# Group_02.net
KiCad netlist of a schematic drawn in EAGLE
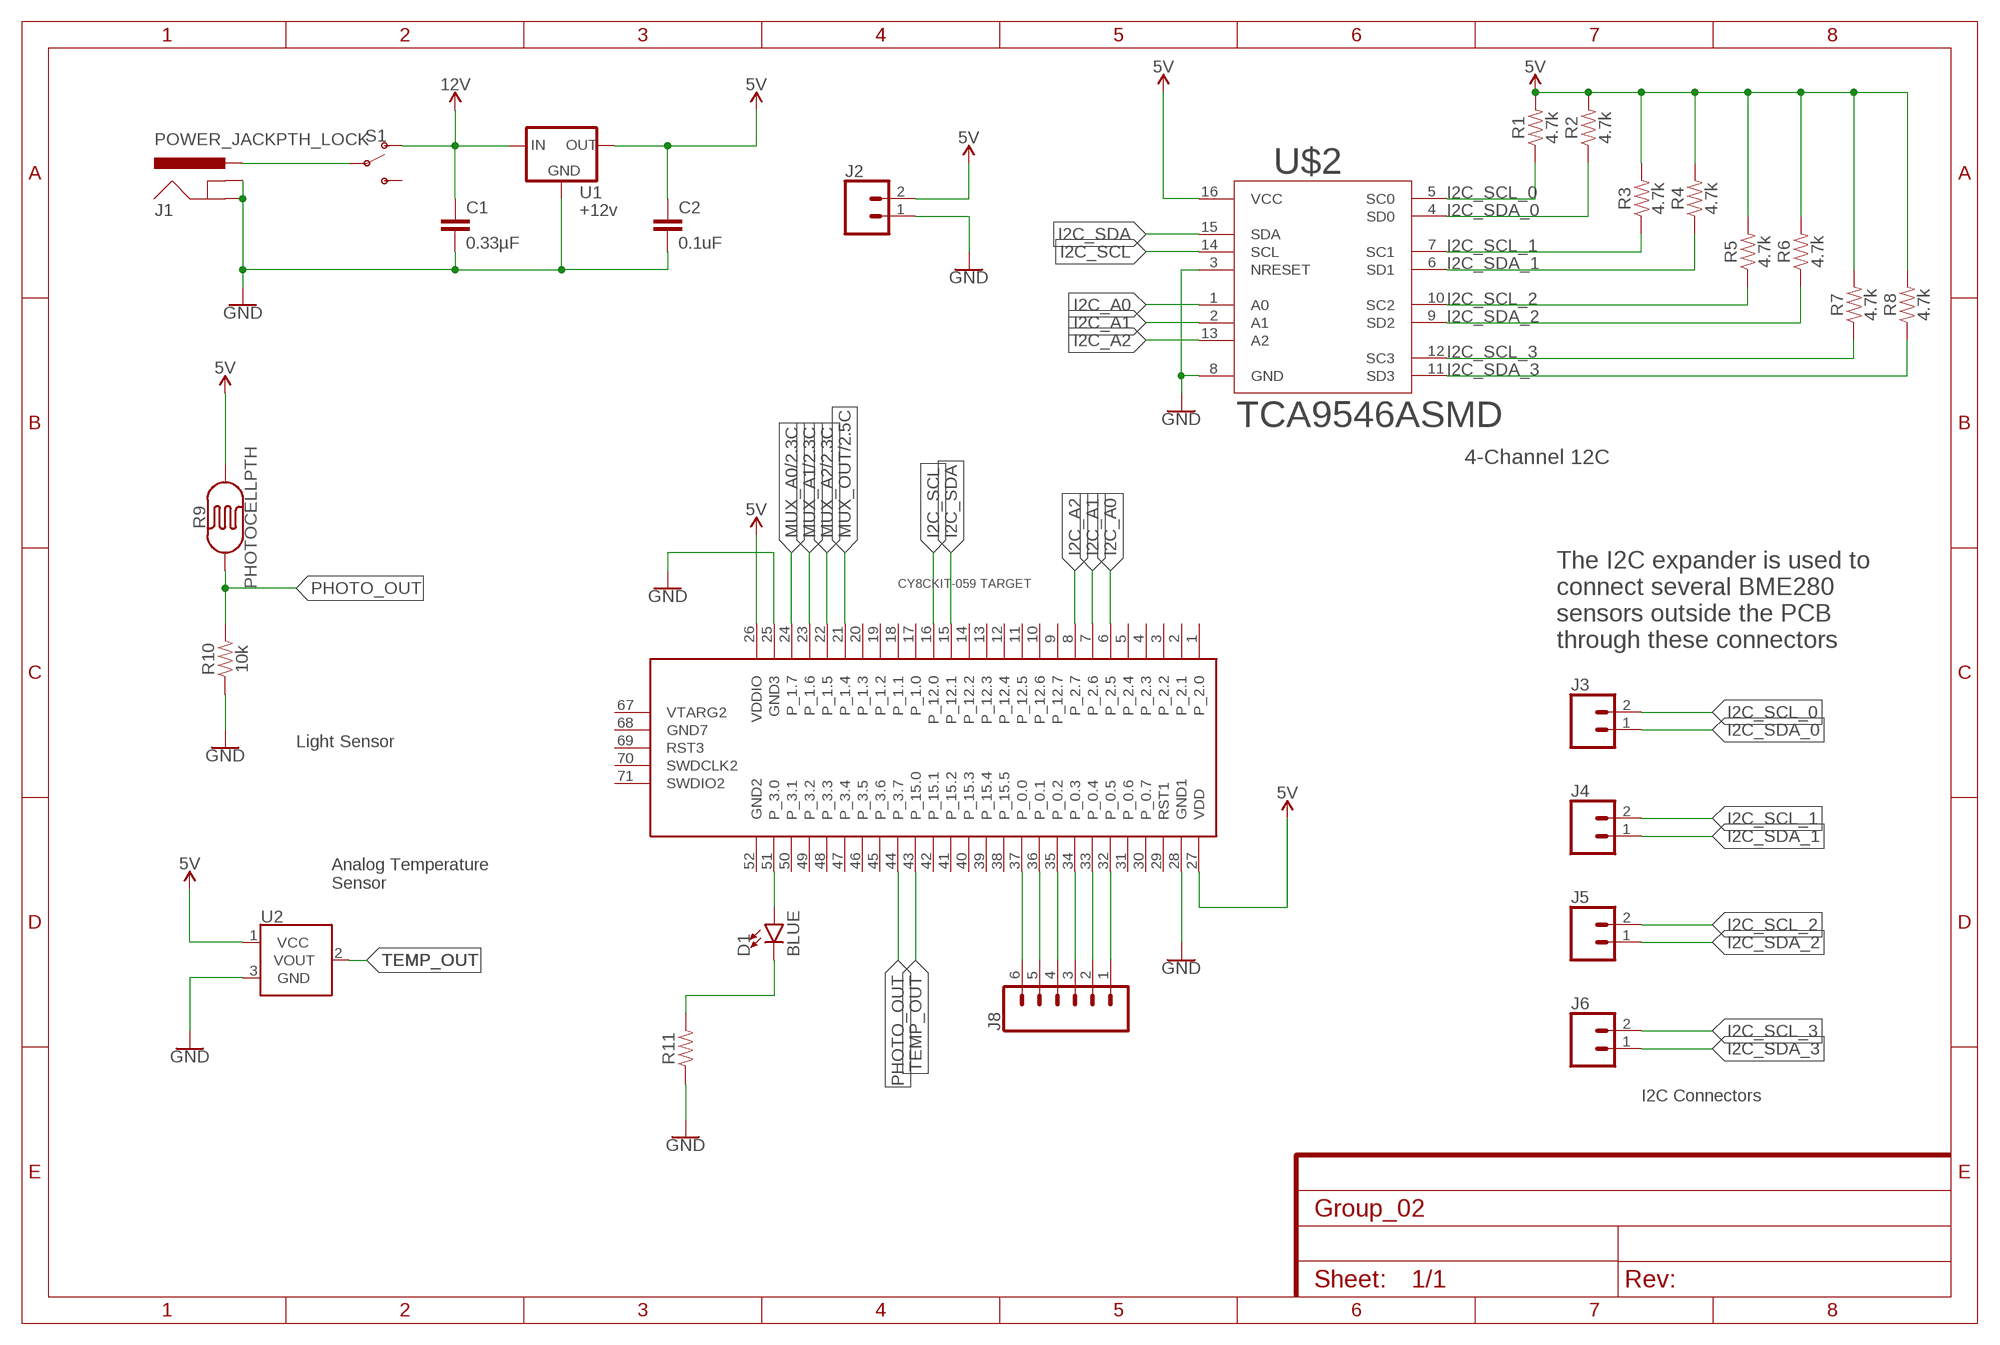
[diagram p0: schematic, sheet 1, part 1 of 2]
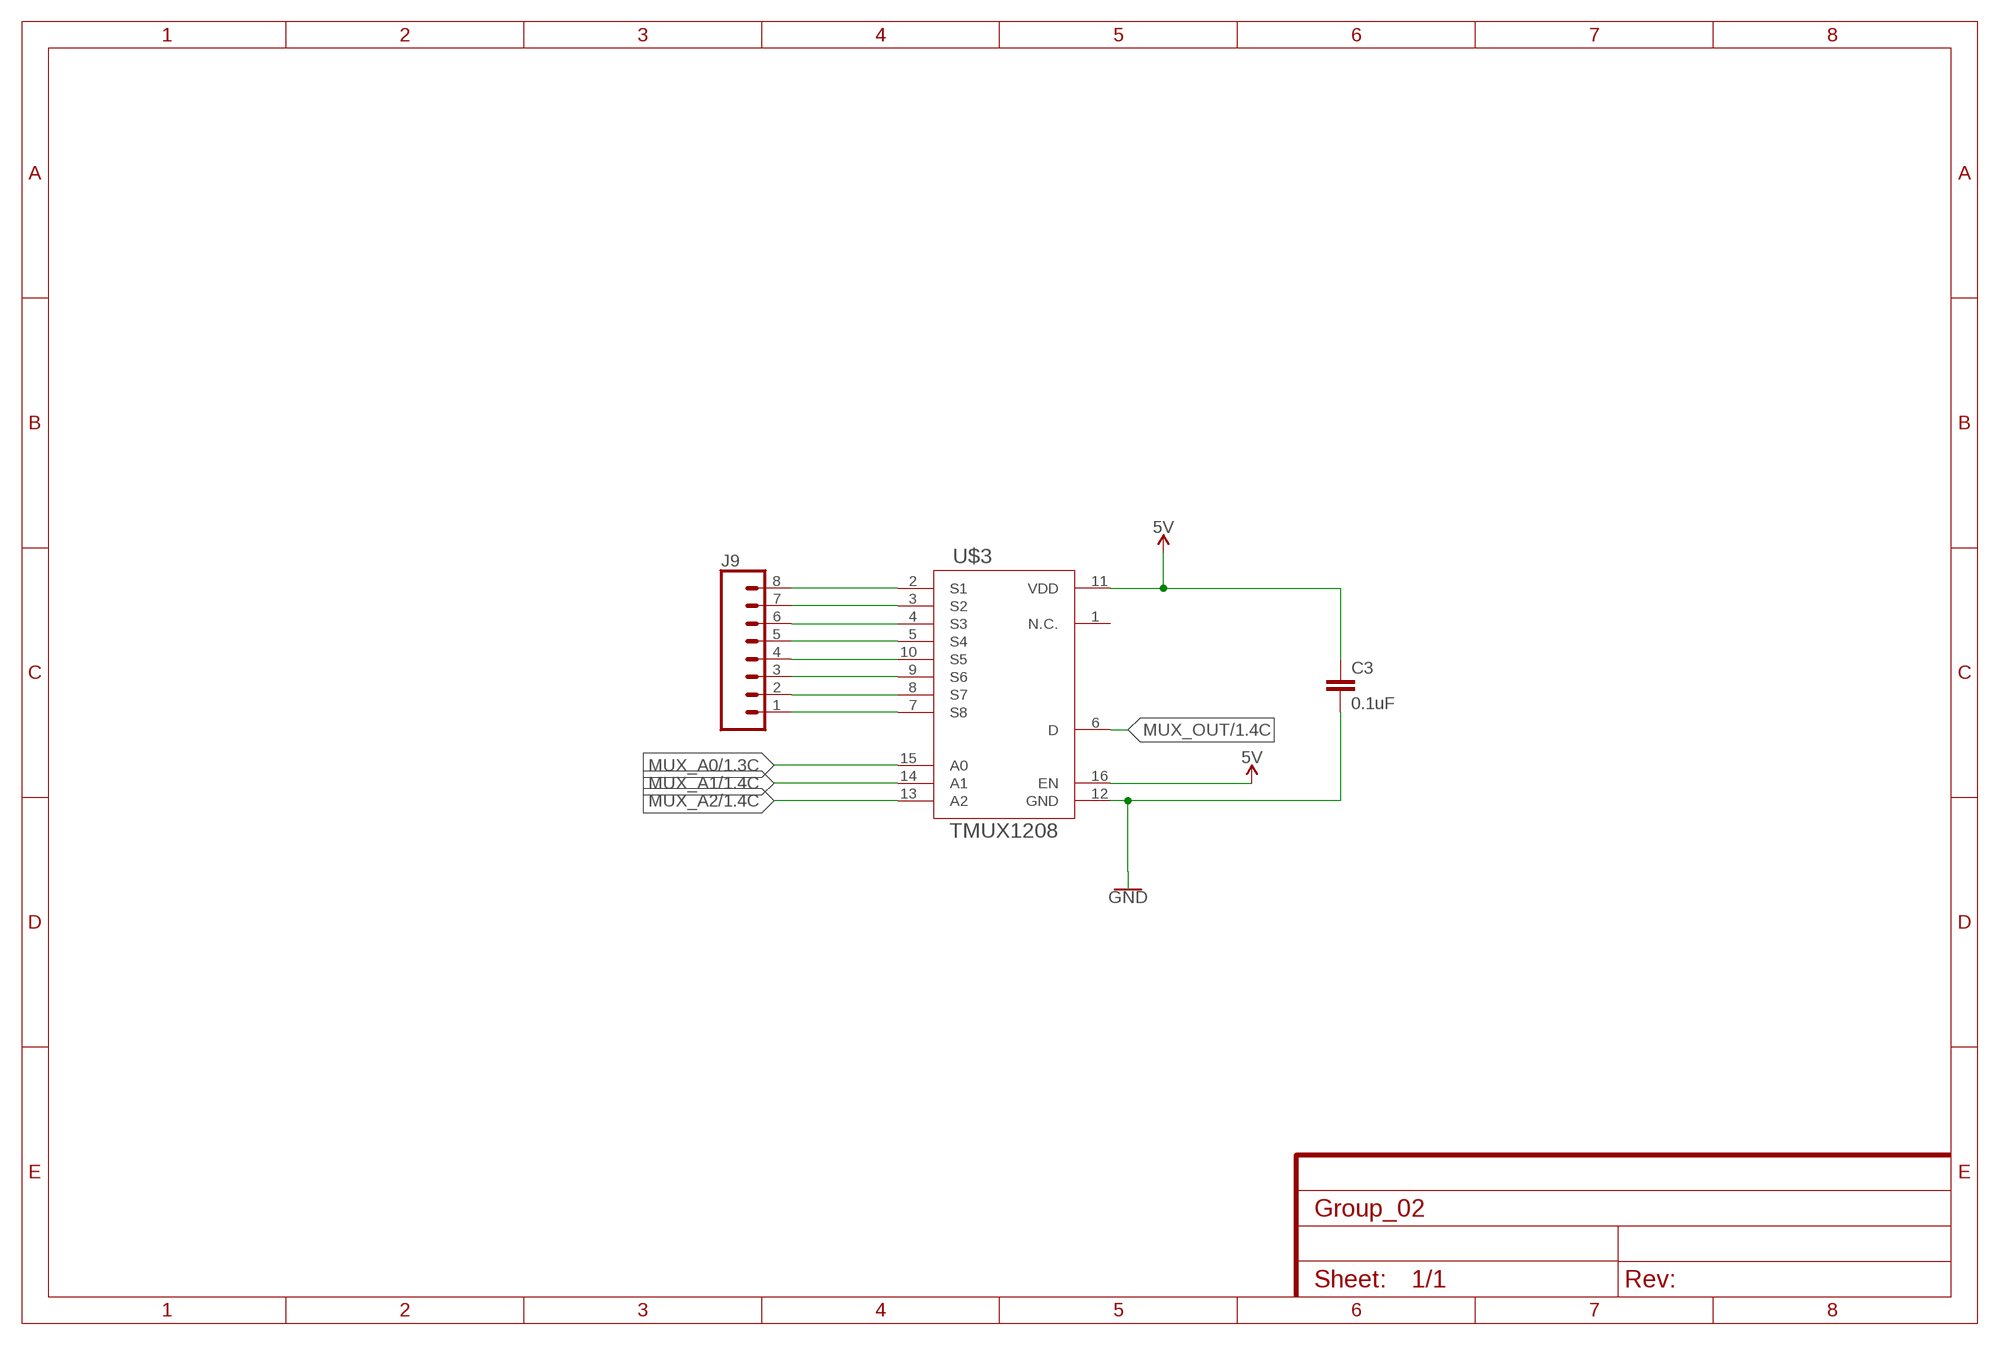
[diagram p1: schematic, sheet 1, part 2 of 2]

(export (version "E")
  (design (tool "Eeschema 10.0.6"))
  (components
    (comp (ref "C1")
      (value "0.33µF")
      (footprint "eagle-import:0805")
      (libsource (lib "eagle-import") (part "0.33UF/330NF-0805-50V-10%"))
    )
    (comp (ref "C2")
      (value "0.1uF")
      (footprint "eagle-import:CAP-PTH-SMALL-KIT")
      (libsource (lib "eagle-import") (part "0.1UF-KIT-EZ-50V-20%"))
    )
    (comp (ref "C3")
      (value "0.1uF")
      (footprint "eagle-import:CAP-PTH-SMALL-KIT")
      (libsource (lib "eagle-import") (part "0.1UF-KIT-EZ-50V-20%"))
    )
    (comp (ref "D1")
      (value "BLUE")
      (footprint "eagle-import:LED-1206")
      (libsource (lib "eagle-import") (part "LED-BLUE1206"))
    )
    (comp (ref "J1")
      (value "POWER_JACKPTH_LOCK")
      (footprint "eagle-import:POWER_JACK_PTH_LOCK")
      (libsource (lib "eagle-import") (part "POWER_JACKPTH_LOCK"))
    )
    (comp (ref "J2")
      (value "CONN_02")
      (footprint "eagle-import:1X02")
      (libsource (lib "eagle-import") (part "CONN_02"))
    )
    (comp (ref "J3")
      (value "CONN_02")
      (footprint "eagle-import:1X02")
      (libsource (lib "eagle-import") (part "CONN_02"))
    )
    (comp (ref "J4")
      (value "CONN_02")
      (footprint "eagle-import:1X02")
      (libsource (lib "eagle-import") (part "CONN_02"))
    )
    (comp (ref "J5")
      (value "CONN_02")
      (footprint "eagle-import:1X02")
      (libsource (lib "eagle-import") (part "CONN_02"))
    )
    (comp (ref "J6")
      (value "CONN_02")
      (footprint "eagle-import:1X02")
      (libsource (lib "eagle-import") (part "CONN_02"))
    )
    (comp (ref "J8")
      (value "CONN_06LOCK")
      (footprint "eagle-import:1X06_LOCK")
      (libsource (lib "eagle-import") (part "CONN_06LOCK"))
    )
    (comp (ref "J9")
      (value "CONN_08LOCK")
      (footprint "eagle-import:1X08_LOCK")
      (libsource (lib "eagle-import") (part "CONN_08LOCK"))
    )
    (comp (ref "R1")
      (value "4.7k")
      (footprint "eagle-import:0603")
      (libsource (lib "eagle-import") (part "4.7KOHM-0603-1/10W-1%"))
    )
    (comp (ref "R2")
      (value "4.7k")
      (footprint "eagle-import:0603")
      (libsource (lib "eagle-import") (part "4.7KOHM-0603-1/10W-1%"))
    )
    (comp (ref "R3")
      (value "4.7k")
      (footprint "eagle-import:0603")
      (libsource (lib "eagle-import") (part "4.7KOHM-0603-1/10W-1%"))
    )
    (comp (ref "R4")
      (value "4.7k")
      (footprint "eagle-import:0603")
      (libsource (lib "eagle-import") (part "4.7KOHM-0603-1/10W-1%"))
    )
    (comp (ref "R5")
      (value "4.7k")
      (footprint "eagle-import:0603")
      (libsource (lib "eagle-import") (part "4.7KOHM-0603-1/10W-1%"))
    )
    (comp (ref "R6")
      (value "4.7k")
      (footprint "eagle-import:0603")
      (libsource (lib "eagle-import") (part "4.7KOHM-0603-1/10W-1%"))
    )
    (comp (ref "R7")
      (value "4.7k")
      (footprint "eagle-import:0603")
      (libsource (lib "eagle-import") (part "4.7KOHM-0603-1/10W-1%"))
    )
    (comp (ref "R8")
      (value "4.7k")
      (footprint "eagle-import:0603")
      (libsource (lib "eagle-import") (part "4.7KOHM-0603-1/10W-1%"))
    )
    (comp (ref "R9")
      (value "PHOTOCELLPTH")
      (footprint "eagle-import:PHOTOCELL")
      (libsource (lib "eagle-import") (part "PHOTOCELLPTH"))
    )
    (comp (ref "R10")
      (value "10k")
      (footprint "eagle-import:0603")
      (libsource (lib "eagle-import") (part "10KOHM-0603-1/10W-1%"))
    )
    (comp (ref "R11")
      (value "RESISTORAXIAL-0.3")
      (footprint "eagle-import:AXIAL-0.3")
      (libsource (lib "eagle-import") (part "RESISTORAXIAL-0.3"))
    )
    (comp (ref "S1")
      (value "SWITCH-SPDT-PTH-11.6X4.0MM")
      (footprint "eagle-import:SWITCH_SPDT_PTH_11.6X4.0MM")
      (libsource (lib "eagle-import") (part "SWITCH-SPDT-PTH-11.6X4.0MM"))
    )
    (comp (ref "U$1")
      (value "CY8CKIT-059_TARGET")
      (footprint "eagle-import:CY8CKIT-059_TARGET")
      (libsource (lib "eagle-import") (part "CY8CKIT-059_TARGET"))
    )
    (comp (ref "U$2")
      (value "TCA9546ASMD")
      (footprint "eagle-import:TSSOP-16")
      (libsource (lib "eagle-import") (part "TCA9546ASMD"))
    )
    (comp (ref "U$3")
      (value "TMUX1208")
      (footprint "eagle-import:QFN-16")
      (libsource (lib "eagle-import") (part "TMUX1208"))
    )
    (comp (ref "U1")
      (value "+12v")
      (footprint "eagle-import:TO-252")
      (libsource (lib "eagle-import") (part "V_REG_78XX7812"))
    )
    (comp (ref "U2")
      (value "TMP36GT9")
      (footprint "eagle-import:TO-92")
      (libsource (lib "eagle-import") (part "TMP36GT9"))
    )
  )
  (nets
    (net (code "1") (name "5V") (class "Default")
      (node (ref "C2") (pin "1") (pinfunction "1_1") (pintype "passive"))
      (node (ref "C3") (pin "1") (pinfunction "1_1") (pintype "passive"))
      (node (ref "J2") (pin "2") (pinfunction "2_2") (pintype "passive"))
      (node (ref "R1") (pin "2") (pinfunction "2_2") (pintype "passive"))
      (node (ref "R2") (pin "2") (pinfunction "2_2") (pintype "passive"))
      (node (ref "R3") (pin "2") (pinfunction "2_2") (pintype "passive"))
      (node (ref "R4") (pin "2") (pinfunction "2_2") (pintype "passive"))
      (node (ref "R5") (pin "2") (pinfunction "2_2") (pintype "passive"))
      (node (ref "R6") (pin "2") (pinfunction "2_2") (pintype "passive"))
      (node (ref "R7") (pin "2") (pinfunction "2_2") (pintype "passive"))
      (node (ref "R8") (pin "2") (pinfunction "2_2") (pintype "passive"))
      (node (ref "R9") (pin "2") (pinfunction "P$2_2") (pintype "bidirectional"))
      (node (ref "U$1") (pin "26") (pinfunction "VDDIO_26") (pintype "bidirectional"))
      (node (ref "U$1") (pin "27") (pinfunction "VDD_27") (pintype "bidirectional"))
      (node (ref "U$2") (pin "16") (pinfunction "VCC_16") (pintype "bidirectional"))
      (node (ref "U$3") (pin "11") (pinfunction "VDD_11") (pintype "bidirectional"))
      (node (ref "U$3") (pin "16") (pinfunction "EN_16") (pintype "bidirectional"))
      (node (ref "U1") (pin "2") (pinfunction "OUT_2") (pintype "passive"))
      (node (ref "U2") (pin "1") (pinfunction "VCC_1") (pintype "bidirectional"))
    )
    (net (code "2") (name "12V") (class "Default")
      (node (ref "C1") (pin "1") (pinfunction "1_1") (pintype "passive"))
      (node (ref "S1") (pin "1") (pinfunction "O_1") (pintype "passive"))
      (node (ref "U1") (pin "1") (pinfunction "IN_1") (pintype "input"))
    )
    (net (code "3") (name "GND") (class "Default")
      (node (ref "C1") (pin "2") (pinfunction "2_2") (pintype "passive"))
      (node (ref "C2") (pin "2") (pinfunction "2_2") (pintype "passive"))
      (node (ref "C3") (pin "2") (pinfunction "2_2") (pintype "passive"))
      (node (ref "J1") (pin "GND") (pinfunction "GND_GND") (pintype "bidirectional"))
      (node (ref "J1") (pin "GNDBREAK") (pinfunction "GNDBREAK_GNDBREAK") (pintype "bidirectional"))
      (node (ref "J2") (pin "1") (pinfunction "1_1") (pintype "passive"))
      (node (ref "R10") (pin "1") (pinfunction "1_1") (pintype "passive"))
      (node (ref "R11") (pin "P$1") (pinfunction "1_P$1") (pintype "passive"))
      (node (ref "U$1") (pin "25") (pinfunction "GND3_25") (pintype "bidirectional"))
      (node (ref "U$1") (pin "28") (pinfunction "GND1_28") (pintype "bidirectional"))
      (node (ref "U$2") (pin "3") (pinfunction "NRESET_3") (pintype "bidirectional"))
      (node (ref "U$2") (pin "8") (pinfunction "GND_8") (pintype "bidirectional"))
      (node (ref "U$3") (pin "12") (pinfunction "GND_12") (pintype "bidirectional"))
      (node (ref "U1") (pin "3") (pinfunction "GND_3") (pintype "input"))
      (node (ref "U2") (pin "3") (pinfunction "GND_3") (pintype "bidirectional"))
    )
    (net (code "4") (name "I2C_A0") (class "Default")
      (node (ref "U$1") (pin "6") (pinfunction "P_2.5_6") (pintype "bidirectional"))
      (node (ref "U$2") (pin "1") (pinfunction "A0_1") (pintype "bidirectional"))
    )
    (net (code "5") (name "I2C_A1") (class "Default")
      (node (ref "U$1") (pin "7") (pinfunction "P_2.6_7") (pintype "bidirectional"))
      (node (ref "U$2") (pin "2") (pinfunction "A1_2") (pintype "bidirectional"))
    )
    (net (code "6") (name "I2C_A2") (class "Default")
      (node (ref "U$1") (pin "8") (pinfunction "P_2.7_8") (pintype "bidirectional"))
      (node (ref "U$2") (pin "13") (pinfunction "A2_13") (pintype "bidirectional"))
    )
    (net (code "7") (name "I2C_SCL") (class "Default")
      (node (ref "U$1") (pin "16") (pinfunction "P_12.0_16") (pintype "bidirectional"))
      (node (ref "U$2") (pin "14") (pinfunction "SCL_14") (pintype "bidirectional"))
    )
    (net (code "8") (name "I2C_SCL_0") (class "Default")
      (node (ref "J3") (pin "2") (pinfunction "2_2") (pintype "passive"))
      (node (ref "R1") (pin "1") (pinfunction "1_1") (pintype "passive"))
      (node (ref "U$2") (pin "5") (pinfunction "SC0_5") (pintype "bidirectional"))
    )
    (net (code "9") (name "I2C_SCL_1") (class "Default")
      (node (ref "J4") (pin "2") (pinfunction "2_2") (pintype "passive"))
      (node (ref "R3") (pin "1") (pinfunction "1_1") (pintype "passive"))
      (node (ref "U$2") (pin "7") (pinfunction "SC1_7") (pintype "bidirectional"))
    )
    (net (code "10") (name "I2C_SCL_2") (class "Default")
      (node (ref "J5") (pin "2") (pinfunction "2_2") (pintype "passive"))
      (node (ref "R5") (pin "1") (pinfunction "1_1") (pintype "passive"))
      (node (ref "U$2") (pin "10") (pinfunction "SC2_10") (pintype "bidirectional"))
    )
    (net (code "11") (name "I2C_SCL_3") (class "Default")
      (node (ref "J6") (pin "2") (pinfunction "2_2") (pintype "passive"))
      (node (ref "R7") (pin "1") (pinfunction "1_1") (pintype "passive"))
      (node (ref "U$2") (pin "12") (pinfunction "SC3_12") (pintype "bidirectional"))
    )
    (net (code "12") (name "I2C_SDA") (class "Default")
      (node (ref "U$1") (pin "15") (pinfunction "P_12.1_15") (pintype "bidirectional"))
      (node (ref "U$2") (pin "15") (pinfunction "SDA_15") (pintype "bidirectional"))
    )
    (net (code "13") (name "I2C_SDA_0") (class "Default")
      (node (ref "J3") (pin "1") (pinfunction "1_1") (pintype "passive"))
      (node (ref "R2") (pin "1") (pinfunction "1_1") (pintype "passive"))
      (node (ref "U$2") (pin "4") (pinfunction "SD0_4") (pintype "bidirectional"))
    )
    (net (code "14") (name "I2C_SDA_1") (class "Default")
      (node (ref "J4") (pin "1") (pinfunction "1_1") (pintype "passive"))
      (node (ref "R4") (pin "1") (pinfunction "1_1") (pintype "passive"))
      (node (ref "U$2") (pin "6") (pinfunction "SD1_6") (pintype "bidirectional"))
    )
    (net (code "15") (name "I2C_SDA_2") (class "Default")
      (node (ref "J5") (pin "1") (pinfunction "1_1") (pintype "passive"))
      (node (ref "R6") (pin "1") (pinfunction "1_1") (pintype "passive"))
      (node (ref "U$2") (pin "9") (pinfunction "SD2_9") (pintype "bidirectional"))
    )
    (net (code "16") (name "I2C_SDA_3") (class "Default")
      (node (ref "J6") (pin "1") (pinfunction "1_1") (pintype "passive"))
      (node (ref "R8") (pin "1") (pinfunction "1_1") (pintype "passive"))
      (node (ref "U$2") (pin "11") (pinfunction "SD3_11") (pintype "bidirectional"))
    )
    (net (code "17") (name "MUX_A0{slash}1.3C") (class "Default")
      (node (ref "U$3") (pin "15") (pinfunction "A0_15") (pintype "bidirectional"))
    )
    (net (code "18") (name "MUX_A0{slash}2.3C") (class "Default")
      (node (ref "U$1") (pin "24") (pinfunction "P_1.7_24") (pintype "bidirectional"))
    )
    (net (code "19") (name "MUX_A1{slash}1.4C") (class "Default")
      (node (ref "U$3") (pin "14") (pinfunction "A1_14") (pintype "bidirectional"))
    )
    (net (code "20") (name "MUX_A1{slash}2.3C") (class "Default")
      (node (ref "U$1") (pin "23") (pinfunction "P_1.6_23") (pintype "bidirectional"))
    )
    (net (code "21") (name "MUX_A2{slash}1.4C") (class "Default")
      (node (ref "U$3") (pin "13") (pinfunction "A2_13") (pintype "bidirectional"))
    )
    (net (code "22") (name "MUX_A2{slash}2.3C") (class "Default")
      (node (ref "U$1") (pin "22") (pinfunction "P_1.5_22") (pintype "bidirectional"))
    )
    (net (code "23") (name "MUX_OUT{slash}1.4C") (class "Default")
      (node (ref "U$3") (pin "6") (pinfunction "D_6") (pintype "bidirectional"))
    )
    (net (code "24") (name "MUX_OUT{slash}2.5C") (class "Default")
      (node (ref "U$1") (pin "21") (pinfunction "P_1.4_21") (pintype "bidirectional"))
    )
    (net (code "25") (name "Net-(R11-2)") (class "Default")
      (node (ref "D1") (pin "C") (pinfunction "C_C") (pintype "passive"))
      (node (ref "R11") (pin "P$2") (pinfunction "2_P$2") (pintype "passive"))
    )
    (net (code "26") (name "Net-(S1-P)") (class "Default")
      (node (ref "J1") (pin "PWR") (pinfunction "PWR_PWR") (pintype "bidirectional"))
      (node (ref "S1") (pin "2") (pinfunction "P_2") (pintype "passive"))
    )
    (net (code "27") (name "Net-(U$1-P_0.0)") (class "Default")
      (node (ref "J8") (pin "6") (pinfunction "6_6") (pintype "passive"))
      (node (ref "U$1") (pin "37") (pinfunction "P_0.0_37") (pintype "bidirectional"))
    )
    (net (code "28") (name "Net-(U$1-P_0.1)") (class "Default")
      (node (ref "J8") (pin "5") (pinfunction "5_5") (pintype "passive"))
      (node (ref "U$1") (pin "36") (pinfunction "P_0.1_36") (pintype "bidirectional"))
    )
    (net (code "29") (name "Net-(U$1-P_0.2)") (class "Default")
      (node (ref "J8") (pin "4") (pinfunction "4_4") (pintype "passive"))
      (node (ref "U$1") (pin "35") (pinfunction "P_0.2_35") (pintype "bidirectional"))
    )
    (net (code "30") (name "Net-(U$1-P_0.3)") (class "Default")
      (node (ref "J8") (pin "3") (pinfunction "3_3") (pintype "passive"))
      (node (ref "U$1") (pin "34") (pinfunction "P_0.3_34") (pintype "bidirectional"))
    )
    (net (code "31") (name "Net-(U$1-P_0.4)") (class "Default")
      (node (ref "J8") (pin "2") (pinfunction "2_2") (pintype "passive"))
      (node (ref "U$1") (pin "33") (pinfunction "P_0.4_33") (pintype "bidirectional"))
    )
    (net (code "32") (name "Net-(U$1-P_0.5)") (class "Default")
      (node (ref "J8") (pin "1") (pinfunction "1_1") (pintype "passive"))
      (node (ref "U$1") (pin "32") (pinfunction "P_0.5_32") (pintype "bidirectional"))
    )
    (net (code "33") (name "Net-(U$1-P_3.0)") (class "Default")
      (node (ref "D1") (pin "A") (pinfunction "A_A") (pintype "passive"))
      (node (ref "U$1") (pin "51") (pinfunction "P_3.0_51") (pintype "bidirectional"))
    )
    (net (code "34") (name "Net-(U$3-S1)") (class "Default")
      (node (ref "J9") (pin "8") (pinfunction "8_8") (pintype "passive"))
      (node (ref "U$3") (pin "2") (pinfunction "S1_2") (pintype "bidirectional"))
    )
    (net (code "35") (name "Net-(U$3-S2)") (class "Default")
      (node (ref "J9") (pin "7") (pinfunction "7_7") (pintype "passive"))
      (node (ref "U$3") (pin "3") (pinfunction "S2_3") (pintype "bidirectional"))
    )
    (net (code "36") (name "Net-(U$3-S3)") (class "Default")
      (node (ref "J9") (pin "6") (pinfunction "6_6") (pintype "passive"))
      (node (ref "U$3") (pin "4") (pinfunction "S3_4") (pintype "bidirectional"))
    )
    (net (code "37") (name "Net-(U$3-S4)") (class "Default")
      (node (ref "J9") (pin "5") (pinfunction "5_5") (pintype "passive"))
      (node (ref "U$3") (pin "5") (pinfunction "S4_5") (pintype "bidirectional"))
    )
    (net (code "38") (name "Net-(U$3-S5)") (class "Default")
      (node (ref "J9") (pin "4") (pinfunction "4_4") (pintype "passive"))
      (node (ref "U$3") (pin "10") (pinfunction "S5_10") (pintype "bidirectional"))
    )
    (net (code "39") (name "Net-(U$3-S6)") (class "Default")
      (node (ref "J9") (pin "3") (pinfunction "3_3") (pintype "passive"))
      (node (ref "U$3") (pin "9") (pinfunction "S6_9") (pintype "bidirectional"))
    )
    (net (code "40") (name "Net-(U$3-S7)") (class "Default")
      (node (ref "J9") (pin "2") (pinfunction "2_2") (pintype "passive"))
      (node (ref "U$3") (pin "8") (pinfunction "S7_8") (pintype "bidirectional"))
    )
    (net (code "41") (name "Net-(U$3-S8)") (class "Default")
      (node (ref "J9") (pin "1") (pinfunction "1_1") (pintype "passive"))
      (node (ref "U$3") (pin "7") (pinfunction "S8_7") (pintype "bidirectional"))
    )
    (net (code "42") (name "PHOTO_OUT") (class "Default")
      (node (ref "R10") (pin "2") (pinfunction "2_2") (pintype "passive"))
      (node (ref "R9") (pin "1") (pinfunction "P$1_1") (pintype "bidirectional"))
      (node (ref "U$1") (pin "44") (pinfunction "P_3.7_44") (pintype "bidirectional"))
    )
    (net (code "43") (name "TEMP_OUT") (class "Default")
      (node (ref "U$1") (pin "43") (pinfunction "P_15.0_43") (pintype "bidirectional"))
      (node (ref "U2") (pin "2") (pinfunction "VOUT_2") (pintype "bidirectional"))
    )
    (net (code "44") (name "unconnected-(S1-S-Pad3)") (class "Default")
      (node (ref "S1") (pin "3") (pinfunction "S_3") (pintype "passive"))
    )
    (net (code "45") (name "unconnected-(U$1-GND2-Pad52)") (class "Default")
      (node (ref "U$1") (pin "52") (pinfunction "GND2_52") (pintype "bidirectional"))
    )
    (net (code "46") (name "unconnected-(U$1-GND7-Pad68)") (class "Default")
      (node (ref "U$1") (pin "68") (pinfunction "GND7_68") (pintype "bidirectional"))
    )
    (net (code "47") (name "unconnected-(U$1-P_0.6-Pad31)") (class "Default")
      (node (ref "U$1") (pin "31") (pinfunction "P_0.6_31") (pintype "bidirectional"))
    )
    (net (code "48") (name "unconnected-(U$1-P_0.7-Pad30)") (class "Default")
      (node (ref "U$1") (pin "30") (pinfunction "P_0.7_30") (pintype "bidirectional"))
    )
    (net (code "49") (name "unconnected-(U$1-P_1.0-Pad17)") (class "Default")
      (node (ref "U$1") (pin "17") (pinfunction "P_1.0_17") (pintype "bidirectional"))
    )
    (net (code "50") (name "unconnected-(U$1-P_1.1-Pad18)") (class "Default")
      (node (ref "U$1") (pin "18") (pinfunction "P_1.1_18") (pintype "bidirectional"))
    )
    (net (code "51") (name "unconnected-(U$1-P_1.2-Pad19)") (class "Default")
      (node (ref "U$1") (pin "19") (pinfunction "P_1.2_19") (pintype "bidirectional"))
    )
    (net (code "52") (name "unconnected-(U$1-P_1.3-Pad20)") (class "Default")
      (node (ref "U$1") (pin "20") (pinfunction "P_1.3_20") (pintype "bidirectional"))
    )
    (net (code "53") (name "unconnected-(U$1-P_2.0-Pad1)") (class "Default")
      (node (ref "U$1") (pin "1") (pinfunction "P_2.0_1") (pintype "bidirectional"))
    )
    (net (code "54") (name "unconnected-(U$1-P_2.1-Pad2)") (class "Default")
      (node (ref "U$1") (pin "2") (pinfunction "P_2.1_2") (pintype "bidirectional"))
    )
    (net (code "55") (name "unconnected-(U$1-P_2.2-Pad3)") (class "Default")
      (node (ref "U$1") (pin "3") (pinfunction "P_2.2_3") (pintype "bidirectional"))
    )
    (net (code "56") (name "unconnected-(U$1-P_2.3-Pad4)") (class "Default")
      (node (ref "U$1") (pin "4") (pinfunction "P_2.3_4") (pintype "bidirectional"))
    )
    (net (code "57") (name "unconnected-(U$1-P_2.4-Pad5)") (class "Default")
      (node (ref "U$1") (pin "5") (pinfunction "P_2.4_5") (pintype "bidirectional"))
    )
    (net (code "58") (name "unconnected-(U$1-P_3.1-Pad50)") (class "Default")
      (node (ref "U$1") (pin "50") (pinfunction "P_3.1_50") (pintype "bidirectional"))
    )
    (net (code "59") (name "unconnected-(U$1-P_3.2-Pad49)") (class "Default")
      (node (ref "U$1") (pin "49") (pinfunction "P_3.2_49") (pintype "bidirectional"))
    )
    (net (code "60") (name "unconnected-(U$1-P_3.3-Pad48)") (class "Default")
      (node (ref "U$1") (pin "48") (pinfunction "P_3.3_48") (pintype "bidirectional"))
    )
    (net (code "61") (name "unconnected-(U$1-P_3.4-Pad47)") (class "Default")
      (node (ref "U$1") (pin "47") (pinfunction "P_3.4_47") (pintype "bidirectional"))
    )
    (net (code "62") (name "unconnected-(U$1-P_3.5-Pad46)") (class "Default")
      (node (ref "U$1") (pin "46") (pinfunction "P_3.5_46") (pintype "bidirectional"))
    )
    (net (code "63") (name "unconnected-(U$1-P_3.6-Pad45)") (class "Default")
      (node (ref "U$1") (pin "45") (pinfunction "P_3.6_45") (pintype "bidirectional"))
    )
    (net (code "64") (name "unconnected-(U$1-P_12.2-Pad14)") (class "Default")
      (node (ref "U$1") (pin "14") (pinfunction "P_12.2_14") (pintype "bidirectional"))
    )
    (net (code "65") (name "unconnected-(U$1-P_12.3-Pad13)") (class "Default")
      (node (ref "U$1") (pin "13") (pinfunction "P_12.3_13") (pintype "bidirectional"))
    )
    (net (code "66") (name "unconnected-(U$1-P_12.4-Pad12)") (class "Default")
      (node (ref "U$1") (pin "12") (pinfunction "P_12.4_12") (pintype "bidirectional"))
    )
    (net (code "67") (name "unconnected-(U$1-P_12.5-Pad11)") (class "Default")
      (node (ref "U$1") (pin "11") (pinfunction "P_12.5_11") (pintype "bidirectional"))
    )
    (net (code "68") (name "unconnected-(U$1-P_12.6-Pad10)") (class "Default")
      (node (ref "U$1") (pin "10") (pinfunction "P_12.6_10") (pintype "bidirectional"))
    )
    (net (code "69") (name "unconnected-(U$1-P_12.7-Pad9)") (class "Default")
      (node (ref "U$1") (pin "9") (pinfunction "P_12.7_9") (pintype "bidirectional"))
    )
    (net (code "70") (name "unconnected-(U$1-P_15.1-Pad42)") (class "Default")
      (node (ref "U$1") (pin "42") (pinfunction "P_15.1_42") (pintype "bidirectional"))
    )
    (net (code "71") (name "unconnected-(U$1-P_15.2-Pad41)") (class "Default")
      (node (ref "U$1") (pin "41") (pinfunction "P_15.2_41") (pintype "bidirectional"))
    )
    (net (code "72") (name "unconnected-(U$1-P_15.3-Pad40)") (class "Default")
      (node (ref "U$1") (pin "40") (pinfunction "P_15.3_40") (pintype "bidirectional"))
    )
    (net (code "73") (name "unconnected-(U$1-P_15.4-Pad39)") (class "Default")
      (node (ref "U$1") (pin "39") (pinfunction "P_15.4_39") (pintype "bidirectional"))
    )
    (net (code "74") (name "unconnected-(U$1-P_15.5-Pad38)") (class "Default")
      (node (ref "U$1") (pin "38") (pinfunction "P_15.5_38") (pintype "bidirectional"))
    )
    (net (code "75") (name "unconnected-(U$1-RST1-Pad29)") (class "Default")
      (node (ref "U$1") (pin "29") (pinfunction "RST1_29") (pintype "bidirectional"))
    )
    (net (code "76") (name "unconnected-(U$1-RST3-Pad69)") (class "Default")
      (node (ref "U$1") (pin "69") (pinfunction "RST3_69") (pintype "bidirectional"))
    )
    (net (code "77") (name "unconnected-(U$1-SWDCLK2-Pad70)") (class "Default")
      (node (ref "U$1") (pin "70") (pinfunction "SWDCLK2_70") (pintype "bidirectional"))
    )
    (net (code "78") (name "unconnected-(U$1-SWDIO2-Pad71)") (class "Default")
      (node (ref "U$1") (pin "71") (pinfunction "SWDIO2_71") (pintype "bidirectional"))
    )
    (net (code "79") (name "unconnected-(U$1-VTARG2-Pad67)") (class "Default")
      (node (ref "U$1") (pin "67") (pinfunction "VTARG2_67") (pintype "bidirectional"))
    )
    (net (code "80") (name "unconnected-(U$3-N.C.-Pad1)") (class "Default")
      (node (ref "U$3") (pin "1") (pinfunction "N.C._1") (pintype "bidirectional"))
    )
  )
)
